# Sensor_Board_0x01_Test_v1.net
KiCad netlist of a schematic drawn in EAGLE
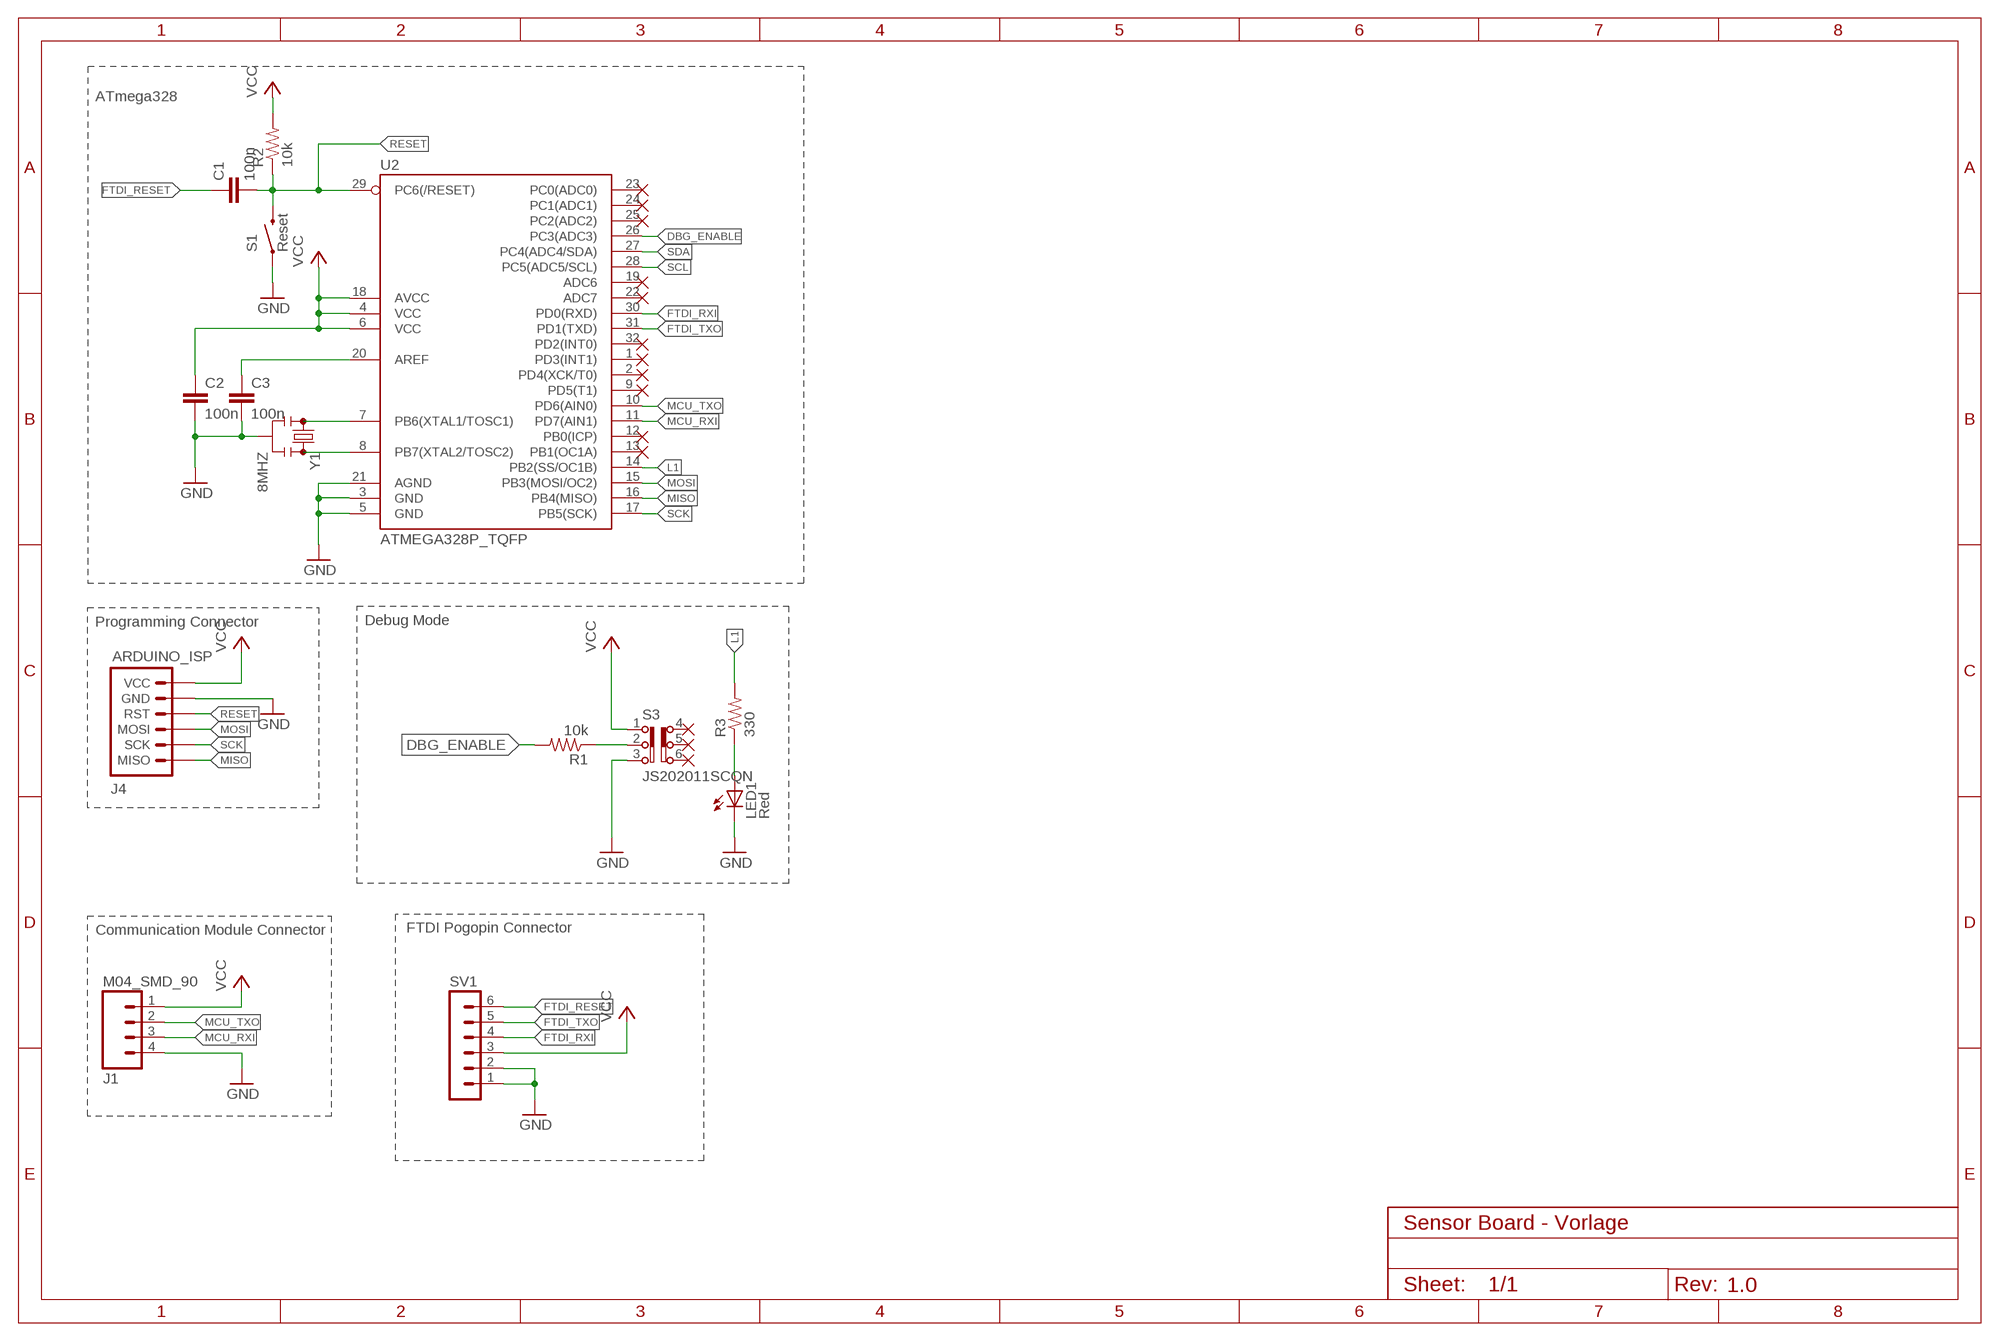
[diagram p0: schematic, sheet 1]

(export (version "E")
  (design (tool "Eeschema 10.0.6"))
  (components
    (comp (ref "C1")
      (value "100n")
      (footprint "eagle-import:C0805")
      (libsource (lib "eagle-import") (part "C"))
    )
    (comp (ref "C2")
      (value "100n")
      (footprint "eagle-import:C0805")
      (libsource (lib "eagle-import") (part "C"))
    )
    (comp (ref "C3")
      (value "100n")
      (footprint "eagle-import:C0805")
      (libsource (lib "eagle-import") (part "C"))
    )
    (comp (ref "J1")
      (value "M04_SMD_90")
      (footprint "eagle-import:M04_SMD_90")
      (libsource (lib "eagle-import") (part "M04_SMD_90"))
    )
    (comp (ref "J4")
      (value "ARDUINO_ISP")
      (footprint "eagle-import:M-2X3")
      (libsource (lib "eagle-import") (part "ARDUINO_ISP"))
    )
    (comp (ref "LED1")
      (value "Red")
      (footprint "eagle-import:SML0805")
      (libsource (lib "eagle-import") (part "LEDSML0805"))
    )
    (comp (ref "R1")
      (value "10k")
      (footprint "eagle-import:0805")
      (libsource (lib "eagle-import") (part "RESISTOR0805-RES"))
    )
    (comp (ref "R2")
      (value "10k")
      (footprint "eagle-import:0805")
      (libsource (lib "eagle-import") (part "RESISTOR0805-RES"))
    )
    (comp (ref "R3")
      (value "330")
      (footprint "eagle-import:0805")
      (libsource (lib "eagle-import") (part "RESISTOR0805-RES"))
    )
    (comp (ref "S1")
      (value "Reset")
      (footprint "eagle-import:M-PUSHBUTTON-SMD")
      (libsource (lib "eagle-import") (part "PUSHBUTTON"))
    )
    (comp (ref "S3")
      (value "JS202011SCQN")
      (footprint "eagle-import:JS202011SCQN")
      (libsource (lib "eagle-import") (part "JS202011SCQN"))
    )
    (comp (ref "SV1")
      (value "MA06-1")
      (footprint "eagle-import:MA06-1")
      (libsource (lib "eagle-import") (part "MA06-1"))
    )
    (comp (ref "U2")
      (value "ATMEGA328P_TQFP")
      (footprint "eagle-import:TQFP32-08")
      (libsource (lib "eagle-import") (part "ATMEGA328P_TQFP"))
    )
    (comp (ref "Y1")
      (value "8MHZ")
      (footprint "eagle-import:RESONATOR-SMD")
      (libsource (lib "eagle-import") (part "RESONATOR8MHZ"))
    )
  )
  (nets
    (net (code "1") (name "DBG_ENABLE") (class "Default")
      (node (ref "R1") (pin "2") (pinfunction "2_2") (pintype "passive"))
      (node (ref "U2") (pin "26") (pinfunction "PC3(ADC3)_26") (pintype "bidirectional"))
    )
    (net (code "2") (name "FTDI_RESET") (class "Default")
      (node (ref "C1") (pin "1") (pinfunction "1_1") (pintype "passive"))
      (node (ref "SV1") (pin "6") (pinfunction "6_6") (pintype "passive"))
    )
    (net (code "3") (name "FTDI_RXI") (class "Default")
      (node (ref "SV1") (pin "4") (pinfunction "4_4") (pintype "passive"))
      (node (ref "U2") (pin "30") (pinfunction "PD0(RXD)_30") (pintype "bidirectional"))
    )
    (net (code "4") (name "FTDI_TXO") (class "Default")
      (node (ref "SV1") (pin "5") (pinfunction "5_5") (pintype "passive"))
      (node (ref "U2") (pin "31") (pinfunction "PD1(TXD)_31") (pintype "bidirectional"))
    )
    (net (code "5") (name "GND") (class "Default")
      (node (ref "C2") (pin "2") (pinfunction "2_2") (pintype "passive"))
      (node (ref "C3") (pin "2") (pinfunction "2_2") (pintype "passive"))
      (node (ref "J1") (pin "4") (pinfunction "4_4") (pintype "passive"))
      (node (ref "J4") (pin "P$5") (pinfunction "GND_P$5") (pintype "passive"))
      (node (ref "LED1") (pin "C") (pinfunction "C_C") (pintype "passive"))
      (node (ref "S1") (pin "1") (pinfunction "LEFT_1") (pintype "passive"))
      (node (ref "S1") (pin "2") (pinfunction "LEFT_2") (pintype "passive"))
      (node (ref "S3") (pin "3") (pinfunction "3_3") (pintype "passive"))
      (node (ref "SV1") (pin "1") (pinfunction "1_1") (pintype "passive"))
      (node (ref "SV1") (pin "2") (pinfunction "2_2") (pintype "passive"))
      (node (ref "U2") (pin "21") (pinfunction "AGND_21") (pintype "bidirectional"))
      (node (ref "U2") (pin "3") (pinfunction "GND_3") (pintype "bidirectional"))
      (node (ref "U2") (pin "5") (pinfunction "GND_5") (pintype "bidirectional"))
      (node (ref "Y1") (pin "2") (pinfunction "2_2") (pintype "passive"))
    )
    (net (code "6") (name "L1") (class "Default")
      (node (ref "R3") (pin "2") (pinfunction "2_2") (pintype "passive"))
      (node (ref "U2") (pin "14") (pinfunction "PB2(SS/OC1B)_14") (pintype "bidirectional"))
    )
    (net (code "7") (name "MCU_RXI") (class "Default")
      (node (ref "J1") (pin "3") (pinfunction "3_3") (pintype "passive"))
      (node (ref "U2") (pin "11") (pinfunction "PD7(AIN1)_11") (pintype "bidirectional"))
    )
    (net (code "8") (name "MCU_TXO") (class "Default")
      (node (ref "J1") (pin "2") (pinfunction "2_2") (pintype "passive"))
      (node (ref "U2") (pin "10") (pinfunction "PD6(AIN0)_10") (pintype "bidirectional"))
    )
    (net (code "9") (name "MISO") (class "Default")
      (node (ref "J4") (pin "P$1") (pinfunction "MISO_P$1") (pintype "passive"))
      (node (ref "U2") (pin "16") (pinfunction "PB4(MISO)_16") (pintype "bidirectional"))
    )
    (net (code "10") (name "MOSI") (class "Default")
      (node (ref "J4") (pin "P$3") (pinfunction "MOSI_P$3") (pintype "passive"))
      (node (ref "U2") (pin "15") (pinfunction "PB3(MOSI/OC2)_15") (pintype "bidirectional"))
    )
    (net (code "11") (name "Net-(LED1-PadA)") (class "Default")
      (node (ref "LED1") (pin "A") (pinfunction "A_A") (pintype "passive"))
      (node (ref "R3") (pin "1") (pinfunction "1_1") (pintype "passive"))
    )
    (net (code "12") (name "Net-(R1-Pad1)") (class "Default")
      (node (ref "R1") (pin "1") (pinfunction "1_1") (pintype "passive"))
      (node (ref "S3") (pin "2") (pinfunction "2_2") (pintype "passive"))
    )
    (net (code "13") (name "Net-(U2-AREF)") (class "Default")
      (node (ref "C3") (pin "1") (pinfunction "1_1") (pintype "passive"))
      (node (ref "U2") (pin "20") (pinfunction "AREF_20") (pintype "bidirectional"))
    )
    (net (code "14") (name "Net-(U2-PB6(XTAL1{slash}TOSC1))") (class "Default")
      (node (ref "U2") (pin "7") (pinfunction "PB6(XTAL1/TOSC1)_7") (pintype "bidirectional"))
      (node (ref "Y1") (pin "1") (pinfunction "1_1") (pintype "passive"))
    )
    (net (code "15") (name "Net-(U2-PB7(XTAL2{slash}TOSC2))") (class "Default")
      (node (ref "U2") (pin "8") (pinfunction "PB7(XTAL2/TOSC2)_8") (pintype "bidirectional"))
      (node (ref "Y1") (pin "3") (pinfunction "3_3") (pintype "passive"))
    )
    (net (code "16") (name "RESET") (class "Default")
      (node (ref "C1") (pin "2") (pinfunction "2_2") (pintype "passive"))
      (node (ref "J4") (pin "P$4") (pinfunction "RST_P$4") (pintype "passive"))
      (node (ref "R2") (pin "1") (pinfunction "1_1") (pintype "passive"))
      (node (ref "S1") (pin "3") (pinfunction "RIGHT_3") (pintype "passive"))
      (node (ref "S1") (pin "4") (pinfunction "RIGHT_4") (pintype "passive"))
      (node (ref "U2") (pin "29") (pinfunction "PC6(/RESET)_29") (pintype "bidirectional"))
    )
    (net (code "17") (name "SCK") (class "Default")
      (node (ref "J4") (pin "P$2") (pinfunction "SCK_P$2") (pintype "passive"))
      (node (ref "U2") (pin "17") (pinfunction "PB5(SCK)_17") (pintype "bidirectional"))
    )
    (net (code "18") (name "SCL") (class "Default")
      (node (ref "U2") (pin "28") (pinfunction "PC5(ADC5/SCL)_28") (pintype "bidirectional"))
    )
    (net (code "19") (name "SDA") (class "Default")
      (node (ref "U2") (pin "27") (pinfunction "PC4(ADC4/SDA)_27") (pintype "bidirectional"))
    )
    (net (code "20") (name "VCC") (class "Default")
      (node (ref "C2") (pin "1") (pinfunction "1_1") (pintype "passive"))
      (node (ref "J1") (pin "1") (pinfunction "1_1") (pintype "passive"))
      (node (ref "J4") (pin "P$6") (pinfunction "VCC_P$6") (pintype "passive"))
      (node (ref "R2") (pin "2") (pinfunction "2_2") (pintype "passive"))
      (node (ref "S3") (pin "1") (pinfunction "1_1") (pintype "passive"))
      (node (ref "SV1") (pin "3") (pinfunction "3_3") (pintype "passive"))
      (node (ref "U2") (pin "18") (pinfunction "AVCC_18") (pintype "bidirectional"))
      (node (ref "U2") (pin "4") (pinfunction "VCC_4") (pintype "bidirectional"))
      (node (ref "U2") (pin "6") (pinfunction "VCC_6") (pintype "bidirectional"))
    )
    (net (code "21") (name "unconnected-(S3-Pad4)") (class "Default")
      (node (ref "S3") (pin "4") (pinfunction "4_4") (pintype "passive"))
    )
    (net (code "22") (name "unconnected-(S3-Pad5)") (class "Default")
      (node (ref "S3") (pin "5") (pinfunction "5_5") (pintype "passive"))
    )
    (net (code "23") (name "unconnected-(S3-Pad6)") (class "Default")
      (node (ref "S3") (pin "6") (pinfunction "6_6") (pintype "passive"))
    )
    (net (code "24") (name "unconnected-(U2-ADC6-Pad19)") (class "Default")
      (node (ref "U2") (pin "19") (pinfunction "ADC6_19") (pintype "bidirectional"))
    )
    (net (code "25") (name "unconnected-(U2-ADC7-Pad22)") (class "Default")
      (node (ref "U2") (pin "22") (pinfunction "ADC7_22") (pintype "bidirectional"))
    )
    (net (code "26") (name "unconnected-(U2-PB0(ICP)-Pad12)") (class "Default")
      (node (ref "U2") (pin "12") (pinfunction "PB0(ICP)_12") (pintype "bidirectional"))
    )
    (net (code "27") (name "unconnected-(U2-PB1(OC1A)-Pad13)") (class "Default")
      (node (ref "U2") (pin "13") (pinfunction "PB1(OC1A)_13") (pintype "bidirectional"))
    )
    (net (code "28") (name "unconnected-(U2-PC0(ADC0)-Pad23)") (class "Default")
      (node (ref "U2") (pin "23") (pinfunction "PC0(ADC0)_23") (pintype "bidirectional"))
    )
    (net (code "29") (name "unconnected-(U2-PC1(ADC1)-Pad24)") (class "Default")
      (node (ref "U2") (pin "24") (pinfunction "PC1(ADC1)_24") (pintype "bidirectional"))
    )
    (net (code "30") (name "unconnected-(U2-PC2(ADC2)-Pad25)") (class "Default")
      (node (ref "U2") (pin "25") (pinfunction "PC2(ADC2)_25") (pintype "bidirectional"))
    )
    (net (code "31") (name "unconnected-(U2-PD2(INT0)-Pad32)") (class "Default")
      (node (ref "U2") (pin "32") (pinfunction "PD2(INT0)_32") (pintype "bidirectional"))
    )
    (net (code "32") (name "unconnected-(U2-PD3(INT1)-Pad1)") (class "Default")
      (node (ref "U2") (pin "1") (pinfunction "PD3(INT1)_1") (pintype "bidirectional"))
    )
    (net (code "33") (name "unconnected-(U2-PD4(XCK{slash}T0)-Pad2)") (class "Default")
      (node (ref "U2") (pin "2") (pinfunction "PD4(XCK/T0)_2") (pintype "bidirectional"))
    )
    (net (code "34") (name "unconnected-(U2-PD5(T1)-Pad9)") (class "Default")
      (node (ref "U2") (pin "9") (pinfunction "PD5(T1)_9") (pintype "bidirectional"))
    )
  )
)
